# Photodiode.net
KiCad netlist of a schematic drawn in Altium Designer
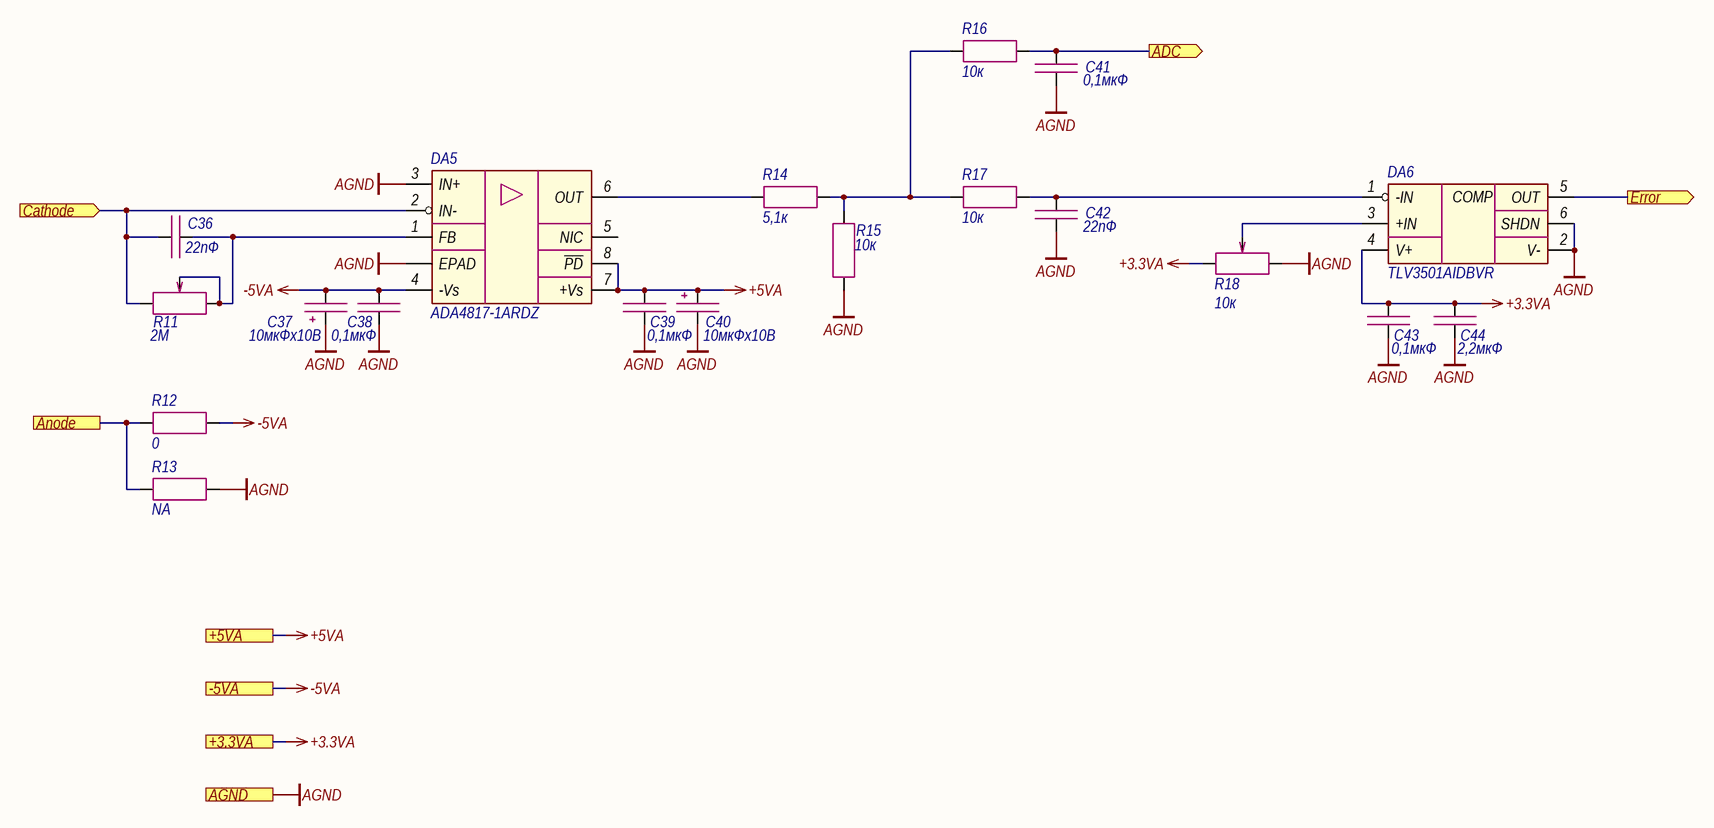
[diagram p0: Photodiode.SchDoc]

(export (version "E")
  (design (tool "Eeschema 10.0.6"))
  (components
    (comp (ref "C36")
      (value "22пФ")
      (footprint "Pcb_library:CAP_0603")
      (fields (field (name "MANUFACTURER") "Murata"))
      (libsource (lib "Schem_library") (part "Capacitor"))
    )
    (comp (ref "C37")
      (value "10мкФх10B")
      (footprint "Pcb_library:CAP_A")
      (libsource (lib "Schem_library") (part "Capacitor_Polar"))
    )
    (comp (ref "C38")
      (value "0,1мкФ")
      (footprint "Pcb_library:CAP_0603")
      (fields (field (name "MANUFACTURER") "Murata"))
      (libsource (lib "Schem_library") (part "Capacitor"))
    )
    (comp (ref "C39")
      (value "0,1мкФ")
      (footprint "Pcb_library:CAP_0603")
      (fields (field (name "MANUFACTURER") "Murata"))
      (libsource (lib "Schem_library") (part "Capacitor"))
    )
    (comp (ref "C40")
      (value "10мкФх10B")
      (footprint "Pcb_library:CAP_A")
      (libsource (lib "Schem_library") (part "Capacitor_Polar"))
    )
    (comp (ref "C41")
      (value "0,1мкФ")
      (footprint "Pcb_library:CAP_0603")
      (fields (field (name "MANUFACTURER") "Murata"))
      (libsource (lib "Schem_library") (part "Capacitor"))
    )
    (comp (ref "C42")
      (value "22пФ")
      (footprint "Pcb_library:CAP_0603")
      (fields (field (name "MANUFACTURER") "Murata"))
      (libsource (lib "Schem_library") (part "Capacitor"))
    )
    (comp (ref "C43")
      (value "0,1мкФ")
      (footprint "Pcb_library:CAP_0603")
      (fields (field (name "MANUFACTURER") "Murata"))
      (libsource (lib "Schem_library") (part "Capacitor"))
    )
    (comp (ref "C44")
      (value "2,2мкФ")
      (footprint "Pcb_library:CAP_0603")
      (fields (field (name "MANUFACTURER") "Murata"))
      (libsource (lib "Schem_library") (part "Capacitor"))
    )
    (comp (ref "DA5")
      (value "ADA4817-1ARDZ")
      (footprint "Pcb_library:SOIC-8 EPAD")
      (fields (field (name "MANUFACTURER") "Analog Devices"))
      (libsource (lib "Schem_library") (part "ADA4817-1ARDZ"))
    )
    (comp (ref "DA6")
      (value "TLV3501AIDBVR")
      (footprint "Pcb_library:SOT-23-6")
      (fields (field (name "MANUFACTURER") "Texas Instruments"))
      (libsource (lib "Schem_library") (part "TLV3501"))
    )
    (comp (ref "R11")
      (value "2М")
      (footprint "Pcb_library:3224W")
      (fields (field (name "MANUFACTURER") "Bourns"))
      (libsource (lib "Schem_library") (part "Resistor_Variable"))
    )
    (comp (ref "R12")
      (value "0")
      (footprint "Pcb_library:RES_0603")
      (fields (field (name "MANUFACTURER") "Yageo"))
      (libsource (lib "Schem_library") (part "Resistor"))
    )
    (comp (ref "R13")
      (value "NA")
      (footprint "Pcb_library:RES_0603")
      (libsource (lib "Schem_library") (part "Resistor"))
    )
    (comp (ref "R14")
      (value "5,1к")
      (footprint "Pcb_library:RES_0603")
      (fields (field (name "MANUFACTURER") "Yageo"))
      (libsource (lib "Schem_library") (part "Resistor"))
    )
    (comp (ref "R15")
      (value "10к")
      (footprint "Pcb_library:RES_0603")
      (fields (field (name "MANUFACTURER") "Yageo"))
      (libsource (lib "Schem_library") (part "Resistor"))
    )
    (comp (ref "R16")
      (value "10к")
      (footprint "Pcb_library:RES_0603")
      (fields (field (name "MANUFACTURER") "Yageo"))
      (libsource (lib "Schem_library") (part "Resistor"))
    )
    (comp (ref "R17")
      (value "10к")
      (footprint "Pcb_library:RES_0603")
      (fields (field (name "MANUFACTURER") "Yageo"))
      (libsource (lib "Schem_library") (part "Resistor"))
    )
    (comp (ref "R18")
      (value "10к")
      (footprint "Pcb_library:3224W")
      (fields (field (name "MANUFACTURER") "Bourns"))
      (libsource (lib "Schem_library") (part "Resistor_Variable"))
    )
  )
  (nets
    (net (code "1") (name "+3.3VA") (class "Default")
      (node (ref "C43") (pin "1") (pinfunction "1_1") (pintype "passive"))
      (node (ref "C44") (pin "1") (pinfunction "1_1") (pintype "passive"))
      (node (ref "DA6") (pin "4") (pinfunction "V+_4") (pintype "passive"))
      (node (ref "R18") (pin "3") (pintype "passive"))
    )
    (net (code "2") (name "+5VA") (class "Default")
      (node (ref "C39") (pin "1") (pinfunction "1_1") (pintype "passive"))
      (node (ref "C40") (pin "1") (pinfunction "1_1") (pintype "passive"))
      (node (ref "DA5") (pin "7") (pinfunction "+Vs_7") (pintype "passive"))
      (node (ref "DA5") (pin "8") (pinfunction "~{PD}_8") (pintype "passive"))
    )
    (net (code "3") (name "-5VA") (class "Default")
      (node (ref "C37") (pin "2") (pinfunction "2_2") (pintype "passive"))
      (node (ref "C38") (pin "1") (pinfunction "1_1") (pintype "passive"))
      (node (ref "DA5") (pin "4") (pinfunction "-Vs_4") (pintype "passive"))
      (node (ref "R12") (pin "1") (pinfunction "1_1") (pintype "passive"))
    )
    (net (code "4") (name "/ADC") (class "Default")
      (node (ref "C41") (pin "1") (pinfunction "1_1") (pintype "passive"))
      (node (ref "R16") (pin "2") (pinfunction "2_2") (pintype "passive"))
    )
    (net (code "5") (name "/Anode") (class "Default")
      (node (ref "R12") (pin "2") (pinfunction "2_2") (pintype "passive"))
      (node (ref "R13") (pin "1") (pinfunction "1_1") (pintype "passive"))
    )
    (net (code "6") (name "/Cathode") (class "Default")
      (node (ref "C36") (pin "2") (pinfunction "2_2") (pintype "passive"))
      (node (ref "DA5") (pin "2") (pinfunction "IN-_2") (pintype "passive"))
      (node (ref "R11") (pin "1") (pintype "passive"))
    )
    (net (code "7") (name "/Error") (class "Default")
      (node (ref "DA6") (pin "5") (pinfunction "OUT_5") (pintype "passive"))
    )
    (net (code "8") (name "AGND") (class "Default")
      (node (ref "C37") (pin "1") (pinfunction "1_1") (pintype "passive"))
      (node (ref "C38") (pin "2") (pinfunction "2_2") (pintype "passive"))
      (node (ref "C39") (pin "2") (pinfunction "2_2") (pintype "passive"))
      (node (ref "C40") (pin "2") (pinfunction "2_2") (pintype "passive"))
      (node (ref "C41") (pin "2") (pinfunction "2_2") (pintype "passive"))
      (node (ref "C42") (pin "2") (pinfunction "2_2") (pintype "passive"))
      (node (ref "C43") (pin "2") (pinfunction "2_2") (pintype "passive"))
      (node (ref "C44") (pin "2") (pinfunction "2_2") (pintype "passive"))
      (node (ref "DA5") (pin "3") (pinfunction "IN+_3") (pintype "passive"))
      (node (ref "DA5") (pin "EPAD") (pinfunction "EPAD_EPAD") (pintype "passive"))
      (node (ref "DA6") (pin "2") (pinfunction "V-_2") (pintype "passive"))
      (node (ref "DA6") (pin "6") (pinfunction "SHDN_6") (pintype "passive"))
      (node (ref "R13") (pin "2") (pinfunction "2_2") (pintype "passive"))
      (node (ref "R15") (pin "2") (pinfunction "2_2") (pintype "passive"))
      (node (ref "R18") (pin "1") (pintype "passive"))
    )
    (net (code "9") (name "Net-(DA5-FB)") (class "Default")
      (node (ref "C36") (pin "1") (pinfunction "1_1") (pintype "passive"))
      (node (ref "DA5") (pin "1") (pinfunction "FB_1") (pintype "passive"))
      (node (ref "R11") (pin "2") (pintype "passive"))
      (node (ref "R11") (pin "3") (pintype "passive"))
    )
    (net (code "10") (name "Net-(DA5-OUT)") (class "Default")
      (node (ref "DA5") (pin "6") (pinfunction "OUT_6") (pintype "passive"))
      (node (ref "R14") (pin "1") (pinfunction "1_1") (pintype "passive"))
    )
    (net (code "11") (name "Net-(DA6-+IN)") (class "Default")
      (node (ref "DA6") (pin "3") (pinfunction "+IN_3") (pintype "passive"))
      (node (ref "R18") (pin "2") (pintype "passive"))
    )
    (net (code "12") (name "Net-(DA6--IN)") (class "Default")
      (node (ref "C42") (pin "1") (pinfunction "1_1") (pintype "passive"))
      (node (ref "DA6") (pin "1") (pinfunction "-IN_1") (pintype "passive"))
      (node (ref "R17") (pin "2") (pinfunction "2_2") (pintype "passive"))
    )
    (net (code "13") (name "Net-(R14-Pad2)") (class "Default")
      (node (ref "R14") (pin "2") (pinfunction "2_2") (pintype "passive"))
      (node (ref "R15") (pin "1") (pinfunction "1_1") (pintype "passive"))
      (node (ref "R16") (pin "1") (pinfunction "1_1") (pintype "passive"))
      (node (ref "R17") (pin "1") (pinfunction "1_1") (pintype "passive"))
    )
    (net (code "14") (name "unconnected-(DA5-NIC-Pad5)") (class "Default")
      (node (ref "DA5") (pin "5") (pinfunction "NIC_5") (pintype "passive"))
    )
  )
)
